# Chassis.net
KiCad netlist of a schematic drawn in EasyEDA Pro
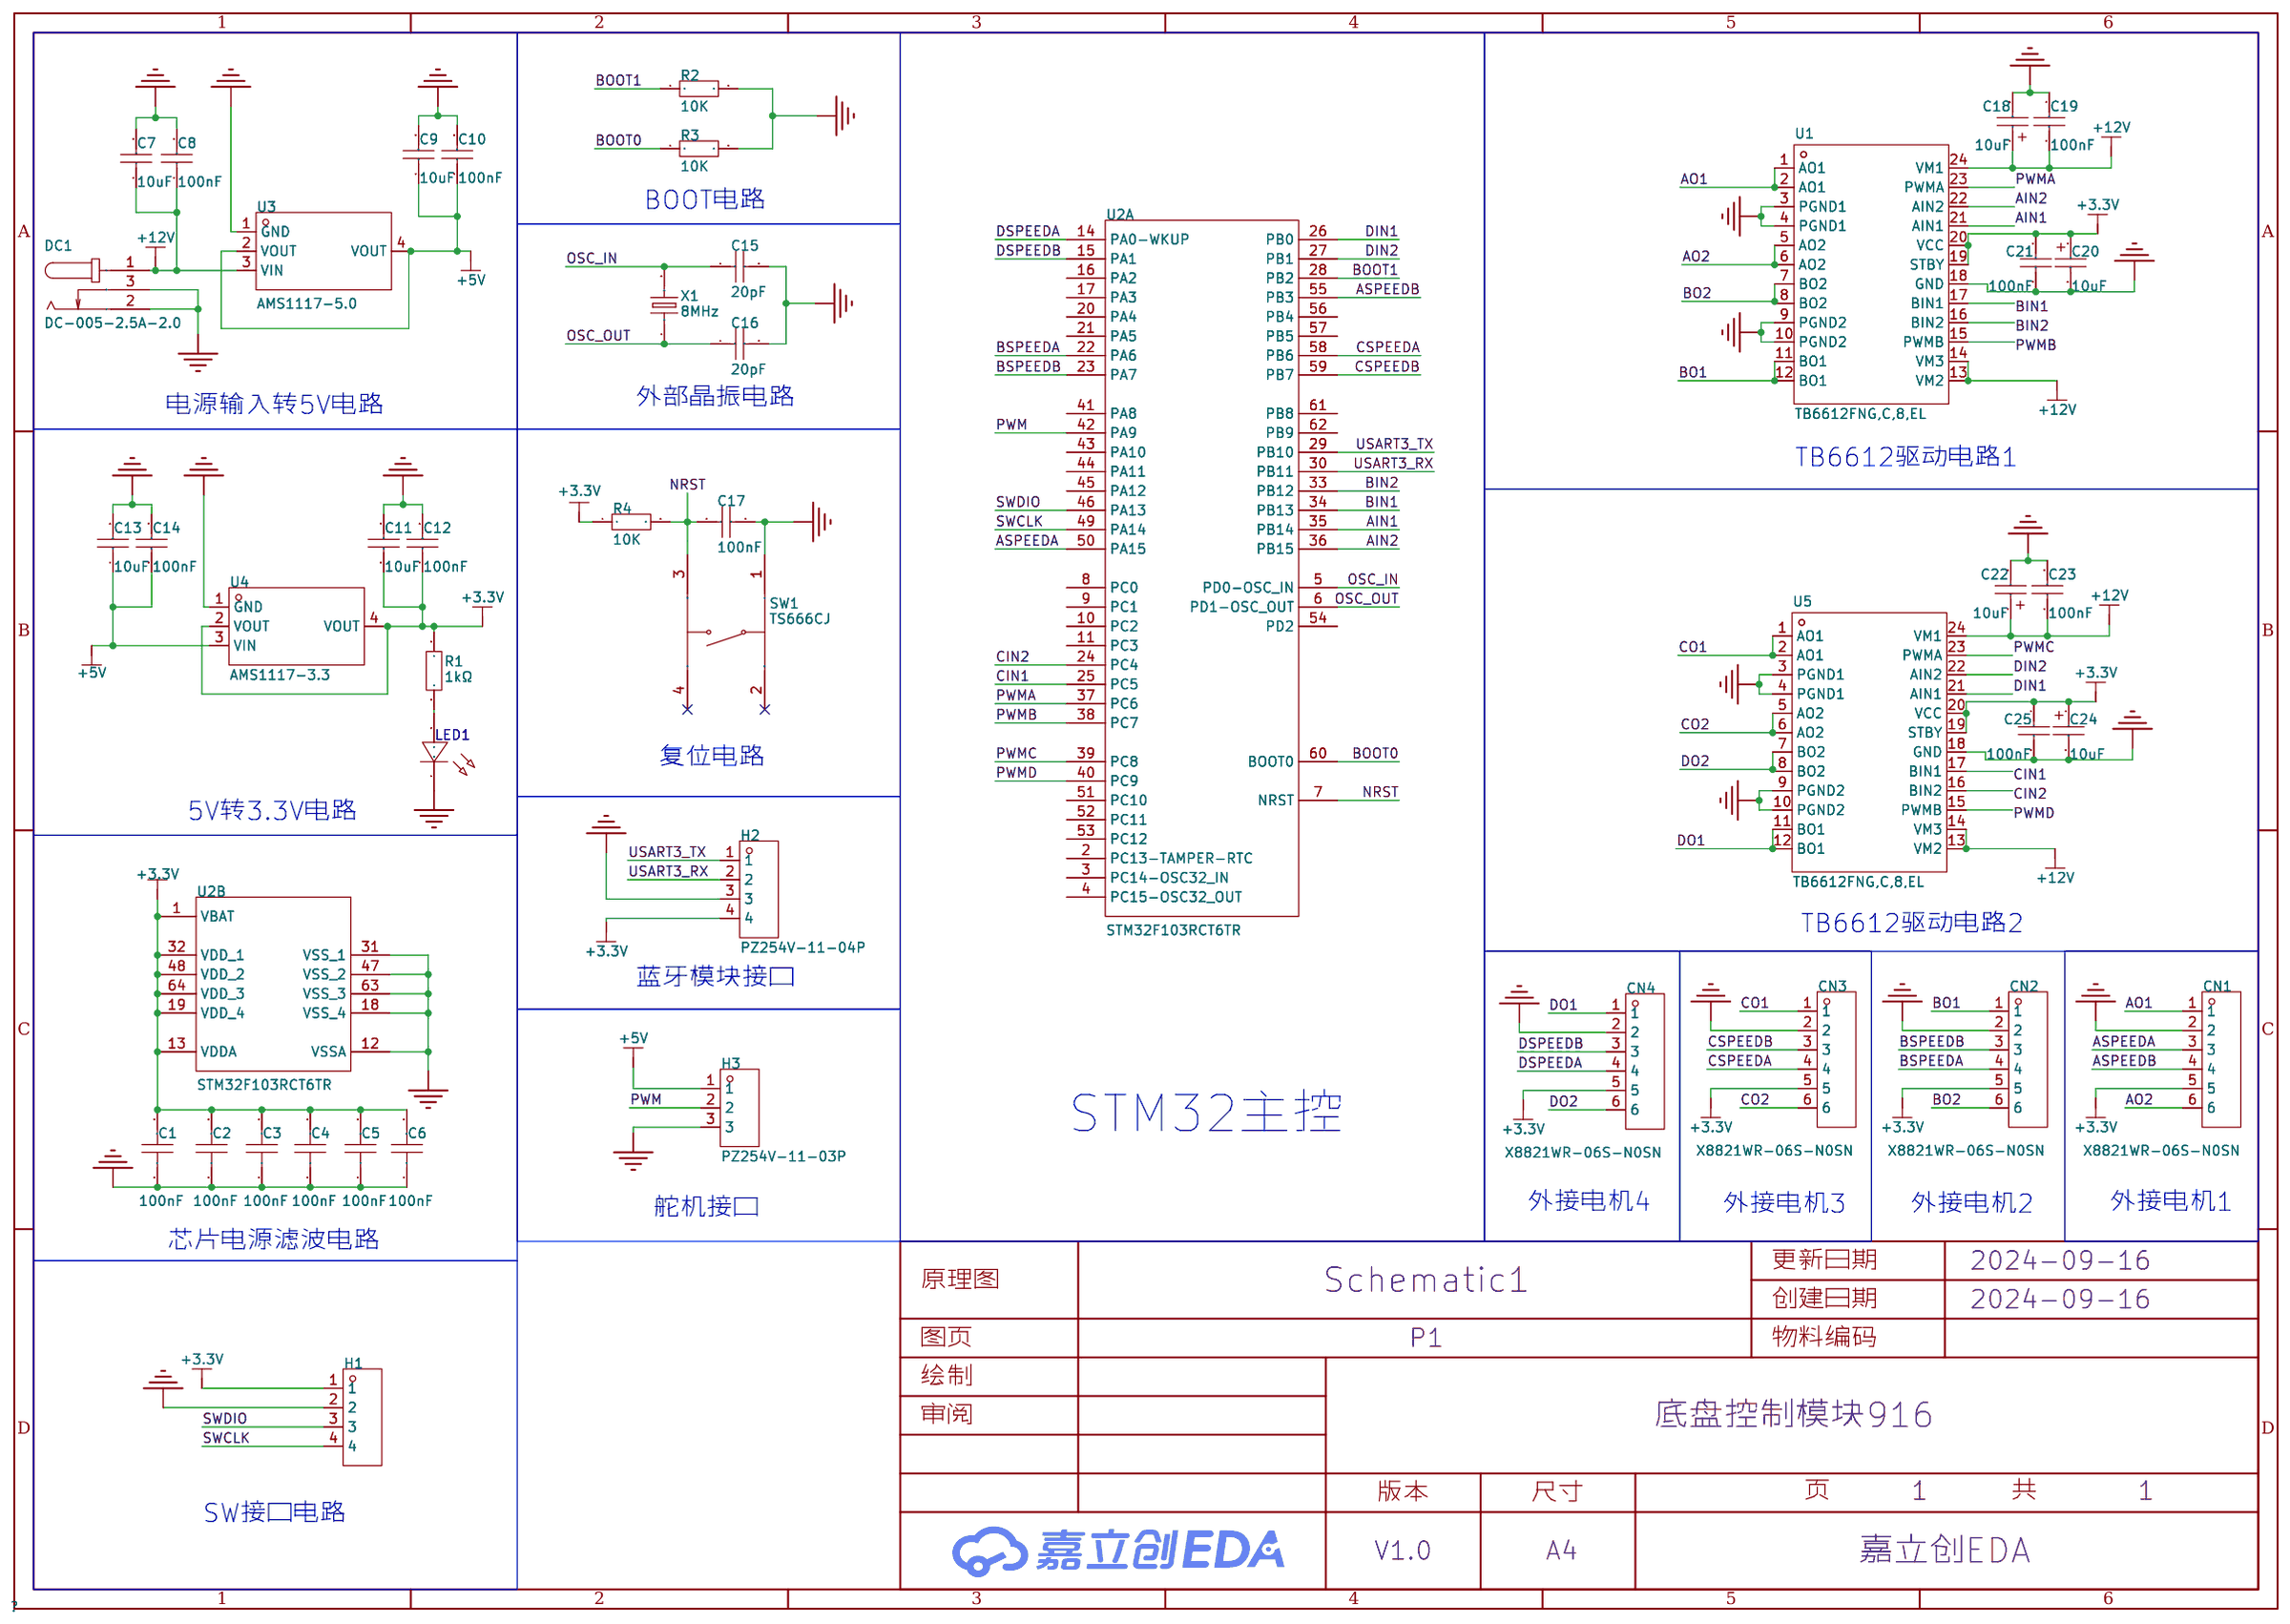
[diagram p0: schematic sheet]

(export (version "E")
  (design (tool "Eeschema 10.0.6"))
  (components
    (comp (ref "C1")
      (value "100nF")
      (footprint "easyedapro:C0603")
      (libsource (lib "easyedapro") (part "CapAcitance"))
    )
    (comp (ref "C2")
      (value "100nF")
      (footprint "easyedapro:C0603")
      (libsource (lib "easyedapro") (part "CapAcitance"))
    )
    (comp (ref "C3")
      (value "100nF")
      (footprint "easyedapro:C0603")
      (libsource (lib "easyedapro") (part "CapAcitance"))
    )
    (comp (ref "C4")
      (value "100nF")
      (footprint "easyedapro:C0603")
      (libsource (lib "easyedapro") (part "CapAcitance"))
    )
    (comp (ref "C5")
      (value "100nF")
      (footprint "easyedapro:C0603")
      (libsource (lib "easyedapro") (part "CapAcitance"))
    )
    (comp (ref "C6")
      (value "100nF")
      (footprint "easyedapro:C0603")
      (libsource (lib "easyedapro") (part "CapAcitance"))
    )
    (comp (ref "C7")
      (value "10uF")
      (footprint "easyedapro:C0402")
      (description "容值:10uF;精度:±20%;额定电压:6.3V;材质(温度系数):X5R;")
      (fields
        (field (name "Manufacturer Part") "CL05A106MQ5NUNC")
        (field (name "Manufacturer") "SAMSUNG(三星)")
      )
      (libsource (lib "easyedapro") (part "CL05A106MQ5NUNC"))
    )
    (comp (ref "C8")
      (value "100nF")
      (footprint "easyedapro:C0402")
      (description "容值:100nF;精度:±10%;额定电压:16V;材质(温度系数):X7R;")
      (fields
        (field (name "Manufacturer Part") "CL05B104KO5NNNC")
        (field (name "Manufacturer") "SAMSUNG(三星)")
      )
      (libsource (lib "easyedapro") (part "CL05B104KO5NNNC"))
    )
    (comp (ref "C9")
      (value "10uF")
      (footprint "easyedapro:C0402")
      (description "容值:10uF;精度:±20%;额定电压:6.3V;材质(温度系数):X5R;")
      (fields
        (field (name "Manufacturer Part") "CL05A106MQ5NUNC")
        (field (name "Manufacturer") "SAMSUNG(三星)")
      )
      (libsource (lib "easyedapro") (part "CL05A106MQ5NUNC"))
    )
    (comp (ref "C10")
      (value "100nF")
      (footprint "easyedapro:C0402")
      (description "容值:100nF;精度:±10%;额定电压:16V;材质(温度系数):X7R;")
      (fields
        (field (name "Manufacturer Part") "CL05B104KO5NNNC")
        (field (name "Manufacturer") "SAMSUNG(三星)")
      )
      (libsource (lib "easyedapro") (part "CL05B104KO5NNNC"))
    )
    (comp (ref "C11")
      (value "10uF")
      (footprint "easyedapro:C0402")
      (description "容值:10uF;精度:±20%;额定电压:6.3V;材质(温度系数):X5R;")
      (fields
        (field (name "Manufacturer Part") "CL05A106MQ5NUNC")
        (field (name "Manufacturer") "SAMSUNG(三星)")
      )
      (libsource (lib "easyedapro") (part "CL05A106MQ5NUNC"))
    )
    (comp (ref "C12")
      (value "100nF")
      (footprint "easyedapro:C0402")
      (description "容值:100nF;精度:±10%;额定电压:16V;材质(温度系数):X7R;")
      (fields
        (field (name "Manufacturer Part") "CL05B104KO5NNNC")
        (field (name "Manufacturer") "SAMSUNG(三星)")
      )
      (libsource (lib "easyedapro") (part "CL05B104KO5NNNC"))
    )
    (comp (ref "C13")
      (value "10uF")
      (footprint "easyedapro:C0402")
      (description "容值:10uF;精度:±20%;额定电压:6.3V;材质(温度系数):X5R;")
      (fields
        (field (name "Manufacturer Part") "CL05A106MQ5NUNC")
        (field (name "Manufacturer") "SAMSUNG(三星)")
      )
      (libsource (lib "easyedapro") (part "CL05A106MQ5NUNC"))
    )
    (comp (ref "C14")
      (value "100nF")
      (footprint "easyedapro:C0402")
      (description "容值:100nF;精度:±10%;额定电压:16V;材质(温度系数):X7R;")
      (fields
        (field (name "Manufacturer Part") "CL05B104KO5NNNC")
        (field (name "Manufacturer") "SAMSUNG(三星)")
      )
      (libsource (lib "easyedapro") (part "CL05B104KO5NNNC"))
    )
    (comp (ref "C15")
      (value "20pF")
      (footprint "easyedapro:C0402")
      (description "容值:20pF;精度:±5%;额定电压:50V;材质(温度系数):C0G;")
      (fields (field (name "Manufacturer Part") "0402CG200J500NT") (field (name "Manufacturer") "FH(风华)"))
      (libsource (lib "easyedapro") (part "0402CG200J500NT"))
    )
    (comp (ref "C16")
      (value "20pF")
      (footprint "easyedapro:C0402")
      (description "容值:20pF;精度:±5%;额定电压:50V;材质(温度系数):C0G;")
      (fields (field (name "Manufacturer Part") "0402CG200J500NT") (field (name "Manufacturer") "FH(风华)"))
      (libsource (lib "easyedapro") (part "0402CG200J500NT"))
    )
    (comp (ref "C17")
      (value "100nF")
      (footprint "easyedapro:C0402")
      (description "容值:100nF;精度:±10%;额定电压:16V;材质(温度系数):X7R;")
      (fields
        (field (name "Manufacturer Part") "CL05B104KO5NNNC")
        (field (name "Manufacturer") "SAMSUNG(三星)")
      )
      (libsource (lib "easyedapro") (part "CL05B104KO5NNNC"))
    )
    (comp (ref "C18")
      (value "10uF")
      (footprint "easyedapro:CAP-SMD_L3.2-W1.6-RD-C7171")
      (description "容值:10uF;精度:±10%;额定电压:16V;等效串联电阻:3Ω@100kHz;")
      (fields (field (name "Manufacturer Part") "TAJA106K016RNJ") (field (name "Manufacturer") "Kyocera AVX"))
      (libsource (lib "easyedapro") (part "TAJA106K016RNJ"))
    )
    (comp (ref "C19")
      (value "100nF")
      (footprint "easyedapro:C0402")
      (description "容值:100nF;精度:±10%;额定电压:16V;材质(温度系数):X7R;")
      (fields
        (field (name "Manufacturer Part") "CL05B104KO5NNNC")
        (field (name "Manufacturer") "SAMSUNG(三星)")
      )
      (libsource (lib "easyedapro") (part "CL05B104KO5NNNC"))
    )
    (comp (ref "C20")
      (value "10uF")
      (footprint "easyedapro:CAP-SMD_L3.2-W1.6-RD-C7171")
      (description "容值:10uF;精度:±10%;额定电压:16V;等效串联电阻:3Ω@100kHz;")
      (fields (field (name "Manufacturer Part") "TAJA106K016RNJ") (field (name "Manufacturer") "Kyocera AVX"))
      (libsource (lib "easyedapro") (part "TAJA106K016RNJ"))
    )
    (comp (ref "C21")
      (value "100nF")
      (footprint "easyedapro:C0402")
      (description "容值:100nF;精度:±10%;额定电压:16V;材质(温度系数):X7R;")
      (fields
        (field (name "Manufacturer Part") "CL05B104KO5NNNC")
        (field (name "Manufacturer") "SAMSUNG(三星)")
      )
      (libsource (lib "easyedapro") (part "CL05B104KO5NNNC"))
    )
    (comp (ref "C22")
      (value "10uF")
      (footprint "easyedapro:CAP-SMD_L3.2-W1.6-RD-C7171")
      (description "容值:10uF;精度:±10%;额定电压:16V;等效串联电阻:3Ω@100kHz;")
      (fields (field (name "Manufacturer Part") "TAJA106K016RNJ") (field (name "Manufacturer") "Kyocera AVX"))
      (libsource (lib "easyedapro") (part "TAJA106K016RNJ"))
    )
    (comp (ref "C23")
      (value "100nF")
      (footprint "easyedapro:C0402")
      (description "容值:100nF;精度:±10%;额定电压:16V;材质(温度系数):X7R;")
      (fields
        (field (name "Manufacturer Part") "CL05B104KO5NNNC")
        (field (name "Manufacturer") "SAMSUNG(三星)")
      )
      (libsource (lib "easyedapro") (part "CL05B104KO5NNNC"))
    )
    (comp (ref "C24")
      (value "10uF")
      (footprint "easyedapro:CAP-SMD_L3.2-W1.6-RD-C7171")
      (description "容值:10uF;精度:±10%;额定电压:16V;等效串联电阻:3Ω@100kHz;")
      (fields (field (name "Manufacturer Part") "TAJA106K016RNJ") (field (name "Manufacturer") "Kyocera AVX"))
      (libsource (lib "easyedapro") (part "TAJA106K016RNJ"))
    )
    (comp (ref "C25")
      (value "100nF")
      (footprint "easyedapro:C0402")
      (description "容值:100nF;精度:±10%;额定电压:16V;材质(温度系数):X7R;")
      (fields
        (field (name "Manufacturer Part") "CL05B104KO5NNNC")
        (field (name "Manufacturer") "SAMSUNG(三星)")
      )
      (libsource (lib "easyedapro") (part "CL05B104KO5NNNC"))
    )
    (comp (ref "CN1")
      (value "X8821WR-06S-N0SN")
      (footprint "easyedapro:CONN-TH_6P-P2.50_X8821WR-06S-N2SN")
      (description "插针结构:1x6P;间距:2.5mm;安装方式:弯插;参考系列:XH;总PIN数:6P;排数:1;每排PIN数:6;行距:-;额定电流:3A;触头材质:黄铜;触头镀层:锡;工作温度范围:-;")
      (fields (field (name "Manufacturer") "XKB Connection(中国星坤)"))
      (libsource (lib "easyedapro") (part "X8821WR-06S-N0SN"))
    )
    (comp (ref "CN2")
      (value "X8821WR-06S-N0SN")
      (footprint "easyedapro:CONN-TH_6P-P2.50_X8821WR-06S-N2SN")
      (description "插针结构:1x6P;间距:2.5mm;安装方式:弯插;参考系列:XH;总PIN数:6P;排数:1;每排PIN数:6;行距:-;额定电流:3A;触头材质:黄铜;触头镀层:锡;工作温度范围:-;")
      (fields (field (name "Manufacturer") "XKB Connection(中国星坤)"))
      (libsource (lib "easyedapro") (part "X8821WR-06S-N0SN"))
    )
    (comp (ref "CN3")
      (value "X8821WR-06S-N0SN")
      (footprint "easyedapro:CONN-TH_6P-P2.50_X8821WR-06S-N2SN")
      (description "插针结构:1x6P;间距:2.5mm;安装方式:弯插;参考系列:XH;总PIN数:6P;排数:1;每排PIN数:6;行距:-;额定电流:3A;触头材质:黄铜;触头镀层:锡;工作温度范围:-;")
      (fields (field (name "Manufacturer") "XKB Connection(中国星坤)"))
      (libsource (lib "easyedapro") (part "X8821WR-06S-N0SN"))
    )
    (comp (ref "CN4")
      (value "X8821WR-06S-N0SN")
      (footprint "easyedapro:CONN-TH_6P-P2.50_X8821WR-06S-N2SN")
      (description "插针结构:1x6P;间距:2.5mm;安装方式:弯插;参考系列:XH;总PIN数:6P;排数:1;每排PIN数:6;行距:-;额定电流:3A;触头材质:黄铜;触头镀层:锡;工作温度范围:-;")
      (fields (field (name "Manufacturer") "XKB Connection(中国星坤)"))
      (libsource (lib "easyedapro") (part "X8821WR-06S-N0SN"))
    )
    (comp (ref "DC1")
      (value "DC-005-2.5A-2.0")
      (footprint "easyedapro:CONN-TH_DC-005-2.5A-2.0")
      (fields (field (name "Manufacturer") "XKB Connection(中国星坤)"))
      (libsource (lib "easyedapro") (part "DC-005-2.5A-2.0"))
    )
    (comp (ref "H1")
      (value "~")
      (footprint "easyedapro:HDR-TH_4P-P2.54-V-M")
      (libsource (lib "easyedapro") (part "PZ254V-11-04P"))
    )
    (comp (ref "H2")
      (value "PZ254V-11-04P")
      (footprint "easyedapro:HDR-TH_4P-P2.54-V-M")
      (fields (field (name "Manufacturer") "XFCN(兴飞)"))
      (libsource (lib "easyedapro") (part "PZ254V-11-04P_C2691448"))
    )
    (comp (ref "H3")
      (value "PZ254V-11-03P")
      (footprint "easyedapro:HDR-TH_3P-P2.54-V-M")
      (fields (field (name "Manufacturer") "XFCN(兴飞)"))
      (libsource (lib "easyedapro") (part "PZ254V-11-03P_C2937625"))
    )
    (comp (ref "LED1")
      (value "~")
      (footprint "easyedapro:LED_0805")
      (libsource (lib "easyedapro") (part "LED_B"))
    )
    (comp (ref "R1")
      (value "1kΩ")
      (footprint "easyedapro:R0603")
      (description "电阻类型:厚膜电阻;阻值:1kΩ;精度:±1%;功率:100mW;最大工作电压:75V;温度系数:±100ppm/°C;")
      (fields
        (field (name "Manufacturer Part") "0603WAF1001T5E")
        (field (name "Manufacturer") "UNI-ROYAL(厚声)")
      )
      (libsource (lib "easyedapro") (part "0603WAF1001T5E"))
    )
    (comp (ref "R2") (value "10K") (footprint "easyedapro:R0603") (libsource (lib "easyedapro") (part "电阻")))
    (comp (ref "R3") (value "10K") (footprint "easyedapro:R0603") (libsource (lib "easyedapro") (part "电阻")))
    (comp (ref "R4") (value "10K") (footprint "easyedapro:R0603") (libsource (lib "easyedapro") (part "电阻")))
    (comp (ref "SW1")
      (value "TS666CJ")
      (footprint "easyedapro:SW-TH_4P-L6.0-W6.0-P4.50-LS6.5")
      (fields (field (name "Manufacturer") "SHOU HAN(首韩)"))
      (libsource (lib "easyedapro") (part "TS666CJ"))
    )
    (comp (ref "U1")
      (value "TB6612FNG,C,8,EL")
      (footprint "easyedapro:SSOP-24_L8.3-W5.6-P0.65-LS7.6-BL")
      (fields (field (name "Manufacturer") "TOSHIBA(东芝)"))
      (libsource (lib "easyedapro") (part "TB6612FNG,C,8,EL"))
    )
    (comp (ref "U2")
      (value "STM32F103RCT6TR")
      (footprint "easyedapro:LQFP-64_L10.0-W10.0-P0.50-LS12.0-BL")
      (description "CPU内核:ARM-M3;程序存储容量:256KB;RAM总容量:48KB;GPIO端口数量:51;工作电压范围:2V~3.6V;CPU最大主频:72MHz;程序存储器类型:FLASH;")
      (fields (field (name "Manufacturer") "ST(意法半导体)"))
      (libsource (lib "easyedapro") (part "STM32F103RCT6TR"))
    )
    (comp (ref "U3")
      (value "AMS1117-5.0")
      (footprint "easyedapro:SOT-223_L6.5-W3.5-P2.30-LS7.0-BR")
      (description "输出类型:固定;最大输入电压:12V;输出电压:5V;最大输出电流:1A;电源纹波抑制比(PSRR):68dB@(120Hz);输出极性:正极;")
      (fields (field (name "Manufacturer") "AMS"))
      (libsource (lib "easyedapro") (part "AMS1117-5.0"))
    )
    (comp (ref "U4")
      (value "AMS1117-3.3")
      (footprint "easyedapro:SOT-223-3_L6.5-W3.4-P2.30-LS7.0-BR")
      (description "输出类型:固定;最大输入电压:-;输出电压:3.3V;最大输出电流:1A;电源纹波抑制比(PSRR):72dB@(120Hz);输出极性:正极;")
      (fields (field (name "Manufacturer") "AMS"))
      (libsource (lib "easyedapro") (part "AMS1117-3.3"))
    )
    (comp (ref "U5")
      (value "TB6612FNG,C,8,EL")
      (footprint "easyedapro:SSOP-24_L8.3-W5.6-P0.65-LS7.6-BL")
      (fields (field (name "Manufacturer") "TOSHIBA(东芝)"))
      (libsource (lib "easyedapro") (part "TB6612FNG,C,8,EL"))
    )
    (comp (ref "X1")
      (value "8MHz")
      (footprint "easyedapro:HC-49US_L11.5-W4.5-P4.88")
      (description "晶振类型:直插晶振;频率:8MHz;常温频差:±20ppm;外接负载电容:20pF;频率稳定度(全温):±20ppm;")
      (fields
        (field (name "Manufacturer Part") "49S-8.000-20-20-20/A")
        (field (name "Manufacturer") "LIMING(利明)")
      )
      (libsource (lib "easyedapro") (part "49S-8.000-20-20-20/A"))
    )
  )
  (nets
    (net (code "1") (name "+3.3V") (class "Default")
      (node (ref "C1") (pin "2") (pinfunction "2_2") (pintype "input"))
      (node (ref "C11") (pin "1") (pinfunction "1_1") (pintype "input"))
      (node (ref "C12") (pin "1") (pinfunction "1_1") (pintype "input"))
      (node (ref "C2") (pin "2") (pinfunction "2_2") (pintype "input"))
      (node (ref "C20") (pin "1") (pinfunction "1_1") (pintype "input"))
      (node (ref "C21") (pin "1") (pinfunction "1_1") (pintype "input"))
      (node (ref "C24") (pin "1") (pinfunction "1_1") (pintype "input"))
      (node (ref "C25") (pin "1") (pinfunction "1_1") (pintype "input"))
      (node (ref "C3") (pin "2") (pinfunction "2_2") (pintype "input"))
      (node (ref "C4") (pin "2") (pinfunction "2_2") (pintype "input"))
      (node (ref "C5") (pin "2") (pinfunction "2_2") (pintype "input"))
      (node (ref "C6") (pin "2") (pinfunction "2_2") (pintype "input"))
      (node (ref "CN1") (pin "5") (pinfunction "5_5") (pintype "unspecified"))
      (node (ref "CN2") (pin "5") (pinfunction "5_5") (pintype "unspecified"))
      (node (ref "CN3") (pin "5") (pinfunction "5_5") (pintype "unspecified"))
      (node (ref "CN4") (pin "5") (pinfunction "5_5") (pintype "unspecified"))
      (node (ref "H1") (pin "1") (pinfunction "1_1") (pintype "unspecified"))
      (node (ref "H2") (pin "4") (pinfunction "4_4") (pintype "unspecified"))
      (node (ref "R1") (pin "1") (pinfunction "1_1") (pintype "input"))
      (node (ref "R4") (pin "1") (pinfunction "1_1") (pintype "input"))
      (node (ref "U1") (pin "19") (pinfunction "STBY_19") (pintype "unspecified"))
      (node (ref "U1") (pin "20") (pinfunction "VCC_20") (pintype "unspecified"))
      (node (ref "U2") (pin "1") (pinfunction "VBAT_1") (pintype "unspecified"))
      (node (ref "U2") (pin "13") (pinfunction "VDDA_13") (pintype "unspecified"))
      (node (ref "U2") (pin "19") (pinfunction "VDD_4_19") (pintype "unspecified"))
      (node (ref "U2") (pin "32") (pinfunction "VDD_1_32") (pintype "unspecified"))
      (node (ref "U2") (pin "48") (pinfunction "VDD_2_48") (pintype "unspecified"))
      (node (ref "U2") (pin "64") (pinfunction "VDD_3_64") (pintype "unspecified"))
      (node (ref "U4") (pin "2") (pinfunction "VOUT_2") (pintype "unspecified"))
      (node (ref "U4") (pin "4") (pinfunction "VOUT_4") (pintype "unspecified"))
      (node (ref "U5") (pin "19") (pinfunction "STBY_19") (pintype "unspecified"))
      (node (ref "U5") (pin "20") (pinfunction "VCC_20") (pintype "unspecified"))
    )
    (net (code "2") (name "+5V") (class "Default")
      (node (ref "C10") (pin "1") (pinfunction "1_1") (pintype "input"))
      (node (ref "C13") (pin "1") (pinfunction "1_1") (pintype "input"))
      (node (ref "C14") (pin "1") (pinfunction "1_1") (pintype "input"))
      (node (ref "C9") (pin "1") (pinfunction "1_1") (pintype "input"))
      (node (ref "H3") (pin "1") (pinfunction "1_1") (pintype "unspecified"))
      (node (ref "U3") (pin "2") (pinfunction "VOUT_2") (pintype "unspecified"))
      (node (ref "U3") (pin "4") (pinfunction "VOUT_4") (pintype "unspecified"))
      (node (ref "U4") (pin "3") (pinfunction "VIN_3") (pintype "unspecified"))
    )
    (net (code "3") (name "+12V") (class "Default")
      (node (ref "C18") (pin "1") (pinfunction "1_1") (pintype "input"))
      (node (ref "C19") (pin "1") (pinfunction "1_1") (pintype "input"))
      (node (ref "C22") (pin "1") (pinfunction "1_1") (pintype "input"))
      (node (ref "C23") (pin "1") (pinfunction "1_1") (pintype "input"))
      (node (ref "C7") (pin "1") (pinfunction "1_1") (pintype "input"))
      (node (ref "C8") (pin "1") (pinfunction "1_1") (pintype "input"))
      (node (ref "DC1") (pin "1") (pinfunction "1_1") (pintype "unspecified"))
      (node (ref "U1") (pin "13") (pinfunction "VM2_13") (pintype "unspecified"))
      (node (ref "U1") (pin "14") (pinfunction "VM3_14") (pintype "unspecified"))
      (node (ref "U1") (pin "24") (pinfunction "VM1_24") (pintype "unspecified"))
      (node (ref "U3") (pin "3") (pinfunction "VIN_3") (pintype "unspecified"))
      (node (ref "U5") (pin "13") (pinfunction "VM2_13") (pintype "unspecified"))
      (node (ref "U5") (pin "14") (pinfunction "VM3_14") (pintype "unspecified"))
      (node (ref "U5") (pin "24") (pinfunction "VM1_24") (pintype "unspecified"))
    )
    (net (code "4") (name "/AIN1") (class "Default")
      (node (ref "U1") (pin "21") (pinfunction "AIN1_21") (pintype "unspecified"))
      (node (ref "U2") (pin "35") (pinfunction "PB14_35") (pintype "bidirectional"))
    )
    (net (code "5") (name "/AIN2") (class "Default")
      (node (ref "U1") (pin "22") (pinfunction "AIN2_22") (pintype "unspecified"))
      (node (ref "U2") (pin "36") (pinfunction "PB15_36") (pintype "bidirectional"))
    )
    (net (code "6") (name "/AO1") (class "Default")
      (node (ref "CN1") (pin "1") (pinfunction "1_1") (pintype "unspecified"))
      (node (ref "U1") (pin "1") (pinfunction "AO1_1") (pintype "unspecified"))
      (node (ref "U1") (pin "2") (pinfunction "AO1_2") (pintype "unspecified"))
    )
    (net (code "7") (name "/AO2") (class "Default")
      (node (ref "CN1") (pin "6") (pinfunction "6_6") (pintype "unspecified"))
      (node (ref "U1") (pin "5") (pinfunction "AO2_5") (pintype "unspecified"))
      (node (ref "U1") (pin "6") (pinfunction "AO2_6") (pintype "unspecified"))
    )
    (net (code "8") (name "/ASPEEDA") (class "Default")
      (node (ref "CN1") (pin "3") (pinfunction "3_3") (pintype "unspecified"))
      (node (ref "U2") (pin "50") (pinfunction "PA15_50") (pintype "bidirectional"))
    )
    (net (code "9") (name "/ASPEEDB") (class "Default")
      (node (ref "CN1") (pin "4") (pinfunction "4_4") (pintype "unspecified"))
      (node (ref "U2") (pin "55") (pinfunction "PB3_55") (pintype "bidirectional"))
    )
    (net (code "10") (name "/BIN1") (class "Default")
      (node (ref "U1") (pin "17") (pinfunction "BIN1_17") (pintype "unspecified"))
      (node (ref "U2") (pin "34") (pinfunction "PB13_34") (pintype "bidirectional"))
    )
    (net (code "11") (name "/BIN2") (class "Default")
      (node (ref "U1") (pin "16") (pinfunction "BIN2_16") (pintype "unspecified"))
      (node (ref "U2") (pin "33") (pinfunction "PB12_33") (pintype "bidirectional"))
    )
    (net (code "12") (name "/BO1") (class "Default")
      (node (ref "CN2") (pin "1") (pinfunction "1_1") (pintype "unspecified"))
      (node (ref "U1") (pin "11") (pinfunction "BO1_11") (pintype "unspecified"))
      (node (ref "U1") (pin "12") (pinfunction "BO1_12") (pintype "unspecified"))
    )
    (net (code "13") (name "/BO2") (class "Default")
      (node (ref "CN2") (pin "6") (pinfunction "6_6") (pintype "unspecified"))
      (node (ref "U1") (pin "7") (pinfunction "BO2_7") (pintype "unspecified"))
      (node (ref "U1") (pin "8") (pinfunction "BO2_8") (pintype "unspecified"))
    )
    (net (code "14") (name "/BOOT0") (class "Default")
      (node (ref "R3") (pin "1") (pinfunction "1_1") (pintype "input"))
      (node (ref "U2") (pin "60") (pinfunction "BOOT0_60") (pintype "unspecified"))
    )
    (net (code "15") (name "/BOOT1") (class "Default")
      (node (ref "R2") (pin "1") (pinfunction "1_1") (pintype "input"))
      (node (ref "U2") (pin "28") (pinfunction "PB2_28") (pintype "bidirectional"))
    )
    (net (code "16") (name "/BSPEEDA") (class "Default")
      (node (ref "CN2") (pin "4") (pinfunction "4_4") (pintype "unspecified"))
      (node (ref "U2") (pin "22") (pinfunction "PA6_22") (pintype "bidirectional"))
    )
    (net (code "17") (name "/BSPEEDB") (class "Default")
      (node (ref "CN2") (pin "3") (pinfunction "3_3") (pintype "unspecified"))
      (node (ref "U2") (pin "23") (pinfunction "PA7_23") (pintype "bidirectional"))
    )
    (net (code "18") (name "/CIN1") (class "Default")
      (node (ref "U2") (pin "25") (pinfunction "PC5_25") (pintype "bidirectional"))
      (node (ref "U5") (pin "17") (pinfunction "BIN1_17") (pintype "unspecified"))
    )
    (net (code "19") (name "/CIN2") (class "Default")
      (node (ref "U2") (pin "24") (pinfunction "PC4_24") (pintype "bidirectional"))
      (node (ref "U5") (pin "16") (pinfunction "BIN2_16") (pintype "unspecified"))
    )
    (net (code "20") (name "/CO1") (class "Default")
      (node (ref "CN3") (pin "1") (pinfunction "1_1") (pintype "unspecified"))
      (node (ref "U5") (pin "1") (pinfunction "AO1_1") (pintype "unspecified"))
      (node (ref "U5") (pin "2") (pinfunction "AO1_2") (pintype "unspecified"))
    )
    (net (code "21") (name "/CO2") (class "Default")
      (node (ref "CN3") (pin "6") (pinfunction "6_6") (pintype "unspecified"))
      (node (ref "U5") (pin "5") (pinfunction "AO2_5") (pintype "unspecified"))
      (node (ref "U5") (pin "6") (pinfunction "AO2_6") (pintype "unspecified"))
    )
    (net (code "22") (name "/CSPEEDA") (class "Default")
      (node (ref "CN3") (pin "4") (pinfunction "4_4") (pintype "unspecified"))
      (node (ref "U2") (pin "58") (pinfunction "PB6_58") (pintype "bidirectional"))
    )
    (net (code "23") (name "/CSPEEDB") (class "Default")
      (node (ref "CN3") (pin "3") (pinfunction "3_3") (pintype "unspecified"))
      (node (ref "U2") (pin "59") (pinfunction "PB7_59") (pintype "bidirectional"))
    )
    (net (code "24") (name "/DIN1") (class "Default")
      (node (ref "U2") (pin "26") (pinfunction "PB0_26") (pintype "bidirectional"))
      (node (ref "U5") (pin "21") (pinfunction "AIN1_21") (pintype "unspecified"))
    )
    (net (code "25") (name "/DIN2") (class "Default")
      (node (ref "U2") (pin "27") (pinfunction "PB1_27") (pintype "bidirectional"))
      (node (ref "U5") (pin "22") (pinfunction "AIN2_22") (pintype "unspecified"))
    )
    (net (code "26") (name "/DO1") (class "Default")
      (node (ref "CN4") (pin "1") (pinfunction "1_1") (pintype "unspecified"))
      (node (ref "U5") (pin "11") (pinfunction "BO1_11") (pintype "unspecified"))
      (node (ref "U5") (pin "12") (pinfunction "BO1_12") (pintype "unspecified"))
    )
    (net (code "27") (name "/DO2") (class "Default")
      (node (ref "CN4") (pin "6") (pinfunction "6_6") (pintype "unspecified"))
      (node (ref "U5") (pin "7") (pinfunction "BO2_7") (pintype "unspecified"))
      (node (ref "U5") (pin "8") (pinfunction "BO2_8") (pintype "unspecified"))
    )
    (net (code "28") (name "/DSPEEDA") (class "Default")
      (node (ref "CN4") (pin "4") (pinfunction "4_4") (pintype "unspecified"))
      (node (ref "U2") (pin "14") (pinfunction "PA0-WKUP_14") (pintype "bidirectional"))
    )
    (net (code "29") (name "/DSPEEDB") (class "Default")
      (node (ref "CN4") (pin "3") (pinfunction "3_3") (pintype "unspecified"))
      (node (ref "U2") (pin "15") (pinfunction "PA1_15") (pintype "bidirectional"))
    )
    (net (code "30") (name "/NRST") (class "Default")
      (node (ref "C17") (pin "2") (pinfunction "2_2") (pintype "input"))
      (node (ref "R4") (pin "2") (pinfunction "2_2") (pintype "input"))
      (node (ref "SW1") (pin "3") (pinfunction "C_3") (pintype "input"))
      (node (ref "U2") (pin "7") (pinfunction "NRST_7") (pintype "bidirectional"))
    )
    (net (code "31") (name "/OSC_IN") (class "Default")
      (node (ref "C15") (pin "1") (pinfunction "1_1") (pintype "input"))
      (node (ref "U2") (pin "5") (pinfunction "PD0-OSC_IN_5") (pintype "bidirectional"))
      (node (ref "X1") (pin "2") (pinfunction "2_2") (pintype "input"))
    )
    (net (code "32") (name "/OSC_OUT") (class "Default")
      (node (ref "C16") (pin "1") (pinfunction "1_1") (pintype "input"))
      (node (ref "U2") (pin "6") (pinfunction "PD1-OSC_OUT_6") (pintype "bidirectional"))
      (node (ref "X1") (pin "1") (pinfunction "1_1") (pintype "input"))
    )
    (net (code "33") (name "/PWM") (class "Default")
      (node (ref "H3") (pin "2") (pinfunction "2_2") (pintype "unspecified"))
      (node (ref "U2") (pin "42") (pinfunction "PA9_42") (pintype "bidirectional"))
    )
    (net (code "34") (name "/PWMA") (class "Default")
      (node (ref "U1") (pin "23") (pinfunction "PWMA_23") (pintype "unspecified"))
      (node (ref "U2") (pin "37") (pinfunction "PC6_37") (pintype "bidirectional"))
    )
    (net (code "35") (name "/PWMB") (class "Default")
      (node (ref "U1") (pin "15") (pinfunction "PWMB_15") (pintype "unspecified"))
      (node (ref "U2") (pin "38") (pinfunction "PC7_38") (pintype "bidirectional"))
    )
    (net (code "36") (name "/PWMC") (class "Default")
      (node (ref "U2") (pin "39") (pinfunction "PC8_39") (pintype "bidirectional"))
      (node (ref "U5") (pin "23") (pinfunction "PWMA_23") (pintype "unspecified"))
    )
    (net (code "37") (name "/PWMD") (class "Default")
      (node (ref "U2") (pin "40") (pinfunction "PC9_40") (pintype "bidirectional"))
      (node (ref "U5") (pin "15") (pinfunction "PWMB_15") (pintype "unspecified"))
    )
    (net (code "38") (name "/SWCLK") (class "Default")
      (node (ref "H1") (pin "4") (pinfunction "4_4") (pintype "unspecified"))
      (node (ref "U2") (pin "49") (pinfunction "PA14_49") (pintype "bidirectional"))
    )
    (net (code "39") (name "/SWDIO") (class "Default")
      (node (ref "H1") (pin "3") (pinfunction "3_3") (pintype "unspecified"))
      (node (ref "U2") (pin "46") (pinfunction "PA13_46") (pintype "bidirectional"))
    )
    (net (code "40") (name "/USART3_RX") (class "Default")
      (node (ref "H2") (pin "2") (pinfunction "2_2") (pintype "unspecified"))
      (node (ref "U2") (pin "30") (pinfunction "PB11_30") (pintype "bidirectional"))
    )
    (net (code "41") (name "/USART3_TX") (class "Default")
      (node (ref "H2") (pin "1") (pinfunction "1_1") (pintype "unspecified"))
      (node (ref "U2") (pin "29") (pinfunction "PB10_29") (pintype "bidirectional"))
    )
    (net (code "42") (name "GND") (class "Default")
      (node (ref "C1") (pin "1") (pinfunction "1_1") (pintype "input"))
      (node (ref "C10") (pin "2") (pinfunction "2_2") (pintype "input"))
      (node (ref "C11") (pin "2") (pinfunction "2_2") (pintype "input"))
      (node (ref "C12") (pin "2") (pinfunction "2_2") (pintype "input"))
      (node (ref "C13") (pin "2") (pinfunction "2_2") (pintype "input"))
      (node (ref "C14") (pin "2") (pinfunction "2_2") (pintype "input"))
      (node (ref "C15") (pin "2") (pinfunction "2_2") (pintype "input"))
      (node (ref "C16") (pin "2") (pinfunction "2_2") (pintype "input"))
      (node (ref "C17") (pin "1") (pinfunction "1_1") (pintype "input"))
      (node (ref "C18") (pin "2") (pinfunction "2_2") (pintype "input"))
      (node (ref "C19") (pin "2") (pinfunction "2_2") (pintype "input"))
      (node (ref "C2") (pin "1") (pinfunction "1_1") (pintype "input"))
      (node (ref "C20") (pin "2") (pinfunction "2_2") (pintype "input"))
      (node (ref "C21") (pin "2") (pinfunction "2_2") (pintype "input"))
      (node (ref "C22") (pin "2") (pinfunction "2_2") (pintype "input"))
      (node (ref "C23") (pin "2") (pinfunction "2_2") (pintype "input"))
      (node (ref "C24") (pin "2") (pinfunction "2_2") (pintype "input"))
      (node (ref "C25") (pin "2") (pinfunction "2_2") (pintype "input"))
      (node (ref "C3") (pin "1") (pinfunction "1_1") (pintype "input"))
      (node (ref "C4") (pin "1") (pinfunction "1_1") (pintype "input"))
      (node (ref "C5") (pin "1") (pinfunction "1_1") (pintype "input"))
      (node (ref "C6") (pin "1") (pinfunction "1_1") (pintype "input"))
      (node (ref "C7") (pin "2") (pinfunction "2_2") (pintype "input"))
      (node (ref "C8") (pin "2") (pinfunction "2_2") (pintype "input"))
      (node (ref "C9") (pin "2") (pinfunction "2_2") (pintype "input"))
      (node (ref "CN1") (pin "2") (pinfunction "2_2") (pintype "unspecified"))
      (node (ref "CN2") (pin "2") (pinfunction "2_2") (pintype "unspecified"))
      (node (ref "CN3") (pin "2") (pinfunction "2_2") (pintype "unspecified"))
      (node (ref "CN4") (pin "2") (pinfunction "2_2") (pintype "unspecified"))
      (node (ref "DC1") (pin "2") (pinfunction "2_2") (pintype "unspecified"))
      (node (ref "DC1") (pin "3") (pinfunction "3_3") (pintype "unspecified"))
      (node (ref "H1") (pin "2") (pinfunction "2_2") (pintype "unspecified"))
      (node (ref "H2") (pin "3") (pinfunction "3_3") (pintype "unspecified"))
      (node (ref "H3") (pin "3") (pinfunction "3_3") (pintype "unspecified"))
      (node (ref "LED1") (pin "1") (pinfunction "C_1") (pintype "input"))
      (node (ref "R2") (pin "2") (pinfunction "2_2") (pintype "input"))
      (node (ref "R3") (pin "2") (pinfunction "2_2") (pintype "input"))
      (node (ref "SW1") (pin "1") (pinfunction "A_1") (pintype "input"))
      (node (ref "U1") (pin "10") (pinfunction "PGND2_10") (pintype "unspecified"))
      (node (ref "U1") (pin "18") (pinfunction "GND_18") (pintype "unspecified"))
      (node (ref "U1") (pin "3") (pinfunction "PGND1_3") (pintype "unspecified"))
      (node (ref "U1") (pin "4") (pinfunction "PGND1_4") (pintype "unspecified"))
      (node (ref "U1") (pin "9") (pinfunction "PGND2_9") (pintype "unspecified"))
      (node (ref "U2") (pin "12") (pinfunction "VSSA_12") (pintype "unspecified"))
      (node (ref "U2") (pin "18") (pinfunction "VSS_4_18") (pintype "unspecified"))
      (node (ref "U2") (pin "31") (pinfunction "VSS_1_31") (pintype "unspecified"))
      (node (ref "U2") (pin "47") (pinfunction "VSS_2_47") (pintype "unspecified"))
      (node (ref "U2") (pin "63") (pinfunction "VSS_3_63") (pintype "unspecified"))
      (node (ref "U3") (pin "1") (pinfunction "GND_1") (pintype "unspecified"))
      (node (ref "U4") (pin "1") (pinfunction "GND_1") (pintype "unspecified"))
      (node (ref "U5") (pin "10") (pinfunction "PGND2_10") (pintype "unspecified"))
      (node (ref "U5") (pin "18") (pinfunction "GND_18") (pintype "unspecified"))
      (node (ref "U5") (pin "3") (pinfunction "PGND1_3") (pintype "unspecified"))
      (node (ref "U5") (pin "4") (pinfunction "PGND1_4") (pintype "unspecified"))
      (node (ref "U5") (pin "9") (pinfunction "PGND2_9") (pintype "unspecified"))
    )
    (net (code "43") (name "Net-(LED1-A)") (class "Default")
      (node (ref "LED1") (pin "2") (pinfunction "A_2") (pintype "input"))
      (node (ref "R1") (pin "2") (pinfunction "2_2") (pintype "input"))
    )
    (net (code "44") (name "unconnected-(SW1-B-Pad2)") (class "Default")
      (node (ref "SW1") (pin "2") (pinfunction "B_2") (pintype "input+no_connect"))
    )
    (net (code "45") (name "unconnected-(SW1-D-Pad4)") (class "Default")
      (node (ref "SW1") (pin "4") (pinfunction "D_4") (pintype "input+no_connect"))
    )
    (net (code "46") (name "unconnected-(U2A-PA2-Pad16)") (class "Default")
      (node (ref "U2") (pin "16") (pinfunction "PA2_16") (pintype "bidirectional"))
    )
    (net (code "47") (name "unconnected-(U2A-PA3-Pad17)") (class "Default")
      (node (ref "U2") (pin "17") (pinfunction "PA3_17") (pintype "bidirectional"))
    )
    (net (code "48") (name "unconnected-(U2A-PA4-Pad20)") (class "Default")
      (node (ref "U2") (pin "20") (pinfunction "PA4_20") (pintype "bidirectional"))
    )
    (net (code "49") (name "unconnected-(U2A-PA5-Pad21)") (class "Default")
      (node (ref "U2") (pin "21") (pinfunction "PA5_21") (pintype "bidirectional"))
    )
    (net (code "50") (name "unconnected-(U2A-PA8-Pad41)") (class "Default")
      (node (ref "U2") (pin "41") (pinfunction "PA8_41") (pintype "bidirectional"))
    )
    (net (code "51") (name "unconnected-(U2A-PA10-Pad43)") (class "Default")
      (node (ref "U2") (pin "43") (pinfunction "PA10_43") (pintype "bidirectional"))
    )
    (net (code "52") (name "unconnected-(U2A-PA11-Pad44)") (class "Default")
      (node (ref "U2") (pin "44") (pinfunction "PA11_44") (pintype "bidirectional"))
    )
    (net (code "53") (name "unconnected-(U2A-PA12-Pad45)") (class "Default")
      (node (ref "U2") (pin "45") (pinfunction "PA12_45") (pintype "bidirectional"))
    )
    (net (code "54") (name "unconnected-(U2A-PB4-Pad56)") (class "Default")
      (node (ref "U2") (pin "56") (pinfunction "PB4_56") (pintype "bidirectional"))
    )
    (net (code "55") (name "unconnected-(U2A-PB5-Pad57)") (class "Default")
      (node (ref "U2") (pin "57") (pinfunction "PB5_57") (pintype "bidirectional"))
    )
    (net (code "56") (name "unconnected-(U2A-PB8-Pad61)") (class "Default")
      (node (ref "U2") (pin "61") (pinfunction "PB8_61") (pintype "bidirectional"))
    )
    (net (code "57") (name "unconnected-(U2A-PB9-Pad62)") (class "Default")
      (node (ref "U2") (pin "62") (pinfunction "PB9_62") (pintype "bidirectional"))
    )
    (net (code "58") (name "unconnected-(U2A-PC0-Pad8)") (class "Default")
      (node (ref "U2") (pin "8") (pinfunction "PC0_8") (pintype "bidirectional"))
    )
    (net (code "59") (name "unconnected-(U2A-PC1-Pad9)") (class "Default")
      (node (ref "U2") (pin "9") (pinfunction "PC1_9") (pintype "bidirectional"))
    )
    (net (code "60") (name "unconnected-(U2A-PC2-Pad10)") (class "Default")
      (node (ref "U2") (pin "10") (pinfunction "PC2_10") (pintype "bidirectional"))
    )
    (net (code "61") (name "unconnected-(U2A-PC3-Pad11)") (class "Default")
      (node (ref "U2") (pin "11") (pinfunction "PC3_11") (pintype "bidirectional"))
    )
    (net (code "62") (name "unconnected-(U2A-PC10-Pad51)") (class "Default")
      (node (ref "U2") (pin "51") (pinfunction "PC10_51") (pintype "bidirectional"))
    )
    (net (code "63") (name "unconnected-(U2A-PC11-Pad52)") (class "Default")
      (node (ref "U2") (pin "52") (pinfunction "PC11_52") (pintype "bidirectional"))
    )
    (net (code "64") (name "unconnected-(U2A-PC12-Pad53)") (class "Default")
      (node (ref "U2") (pin "53") (pinfunction "PC12_53") (pintype "bidirectional"))
    )
    (net (code "65") (name "unconnected-(U2A-PC13-TAMPER-RTC-Pad2)") (class "Default")
      (node (ref "U2") (pin "2") (pinfunction "PC13-TAMPER-RTC_2") (pintype "bidirectional"))
    )
    (net (code "66") (name "unconnected-(U2A-PC14-OSC32_IN-Pad3)") (class "Default")
      (node (ref "U2") (pin "3") (pinfunction "PC14-OSC32_IN_3") (pintype "bidirectional"))
    )
    (net (code "67") (name "unconnected-(U2A-PC15-OSC32_OUT-Pad4)") (class "Default")
      (node (ref "U2") (pin "4") (pinfunction "PC15-OSC32_OUT_4") (pintype "bidirectional"))
    )
    (net (code "68") (name "unconnected-(U2A-PD2-Pad54)") (class "Default")
      (node (ref "U2") (pin "54") (pinfunction "PD2_54") (pintype "bidirectional"))
    )
  )
)
